# SCH_Weighing-Scale_2024-06-01.net
KiCad netlist of a schematic drawn in EasyEDA
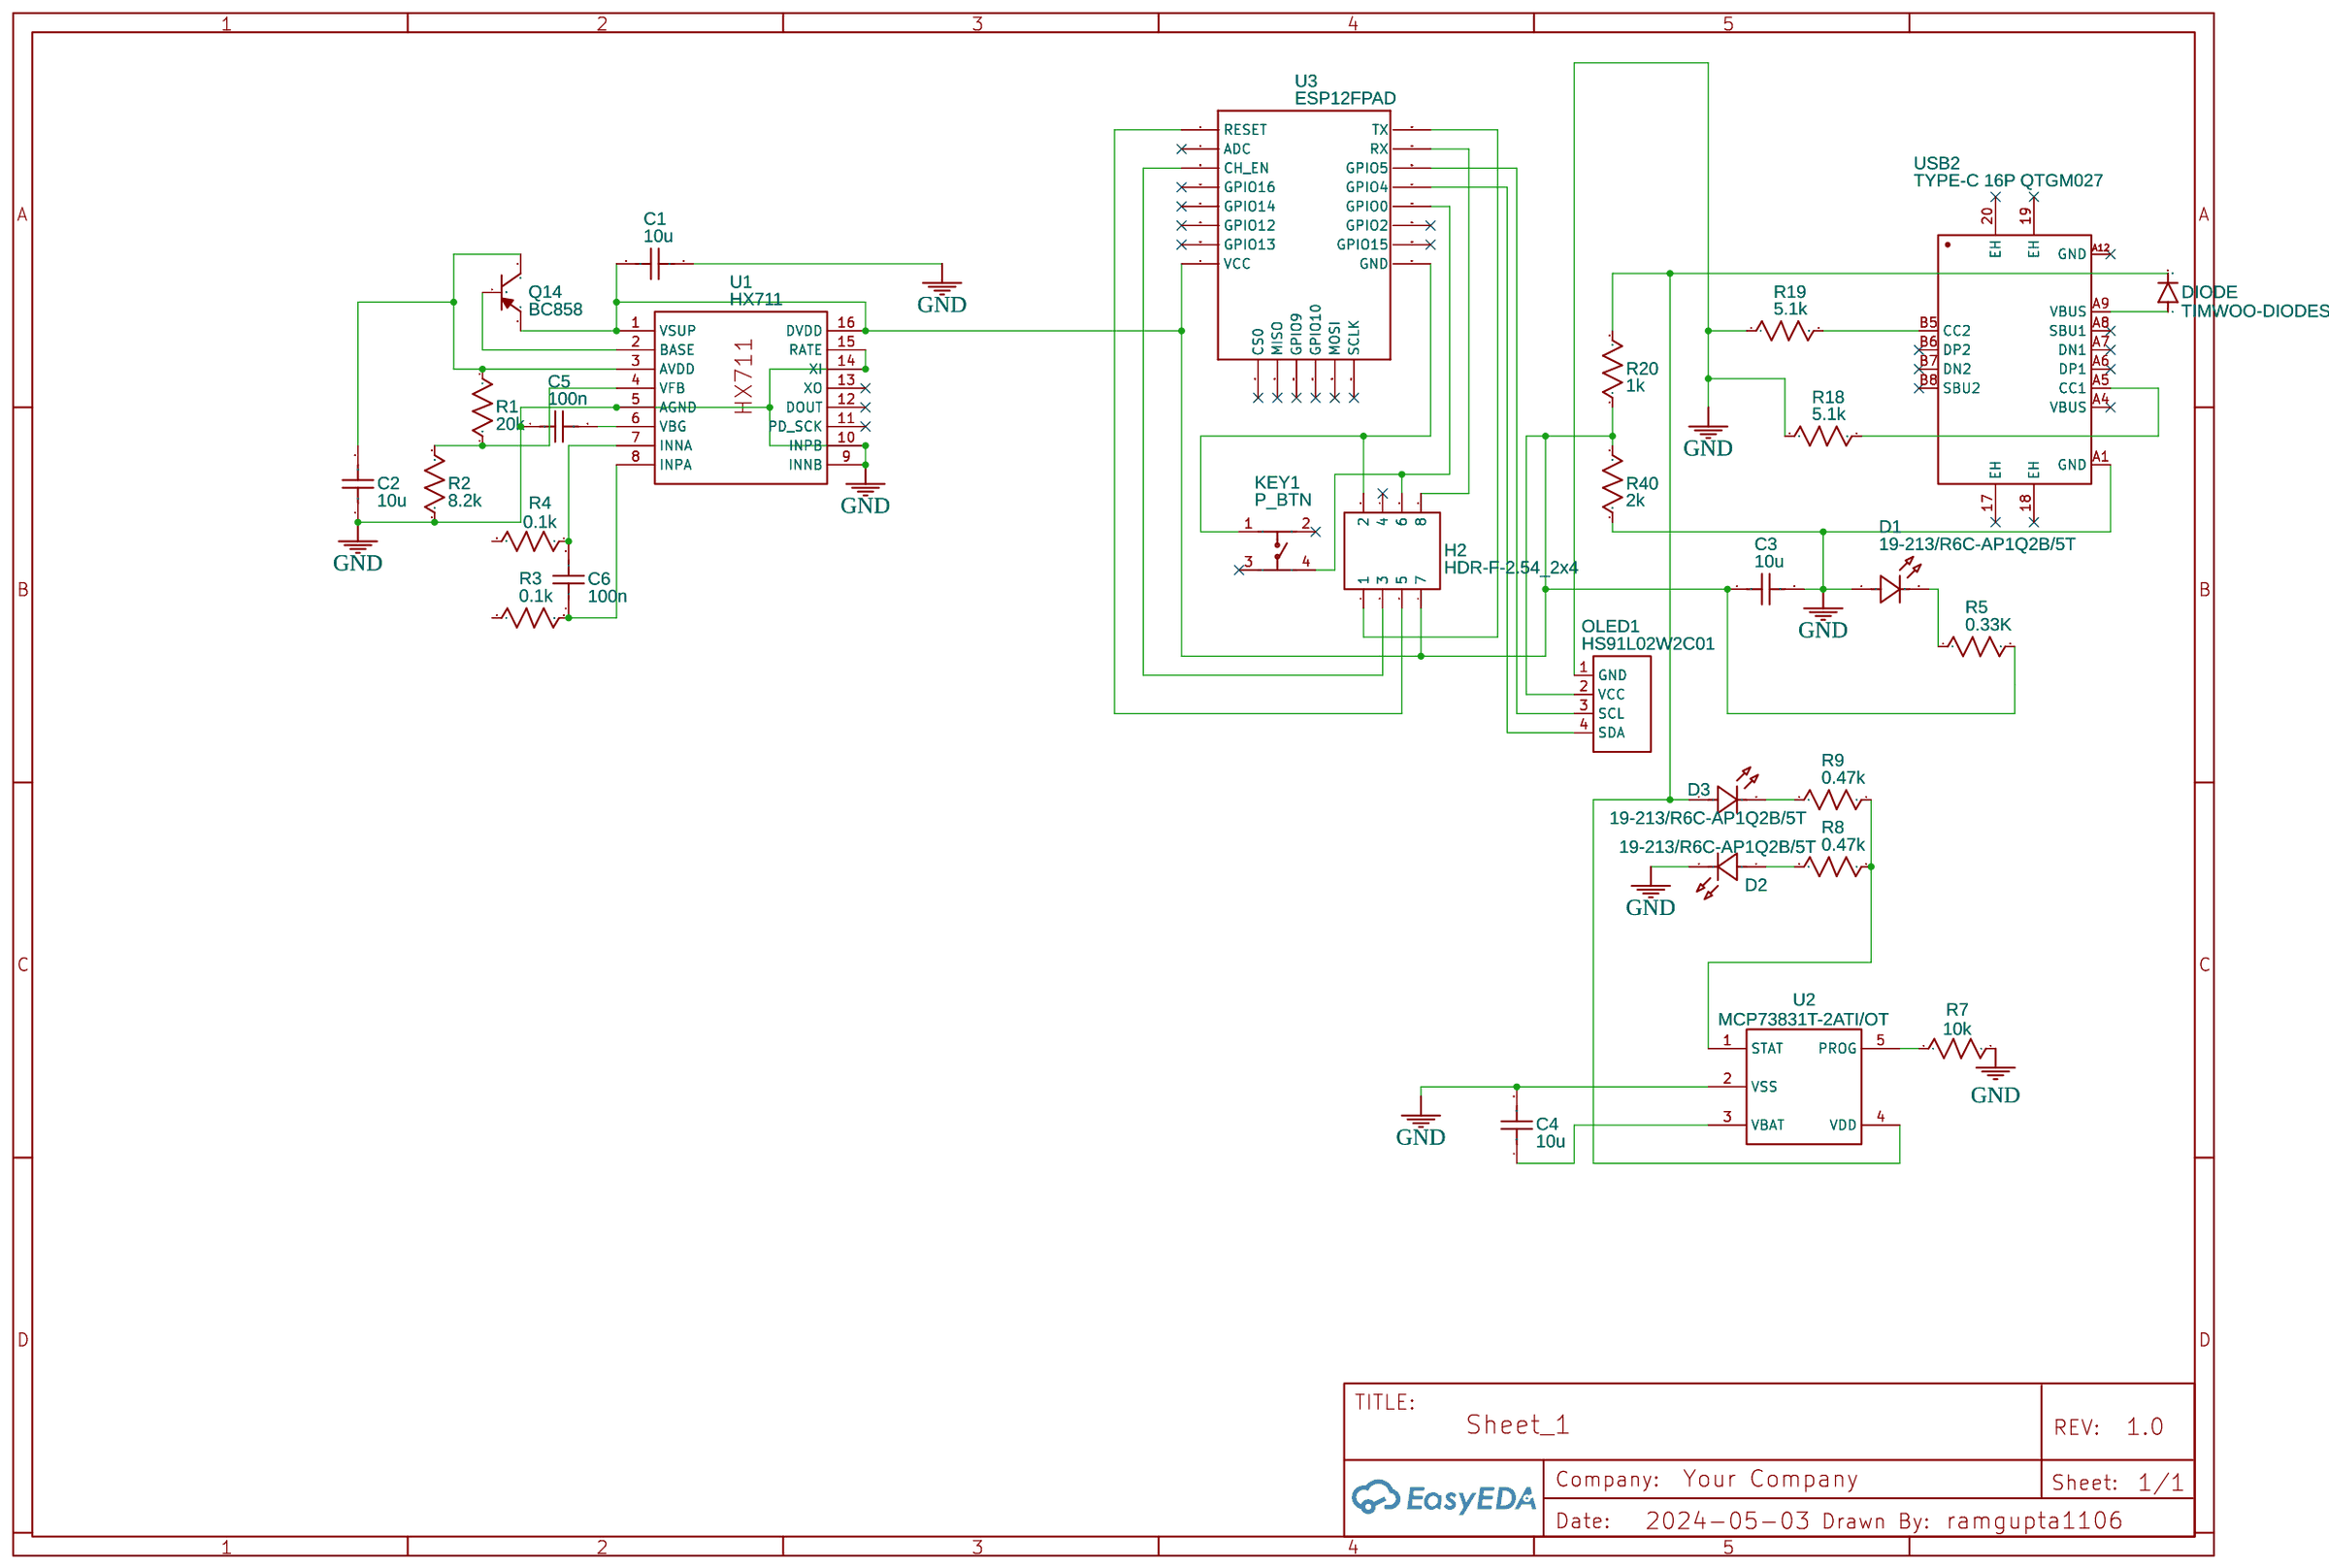
[diagram p0: schematic sheet]

(export (version "E")
  (design (tool "Eeschema 10.0.6"))
  (components
    (comp (ref "C1") (value "10u") (libsource (lib "") (part "C_0603_US_1")))
    (comp (ref "C2") (value "10u") (libsource (lib "") (part "C_0603_US")))
    (comp (ref "C3") (value "10u") (libsource (lib "") (part "C_0603_US_1")))
    (comp (ref "C4") (value "10u") (libsource (lib "") (part "C_0603_US")))
    (comp (ref "C5") (value "100n") (libsource (lib "") (part "C_0603_US_1")))
    (comp (ref "C6") (value "100n") (libsource (lib "") (part "C_0603_US")))
    (comp (ref "D1")
      (value "19-213/R6C-AP1Q2B/5T")
      (fields (field (name "Manufacturer") "EVERLIGHT(亿光)"))
      (libsource (lib "") (part "19-213/R6C-AP1Q2B/5T"))
    )
    (comp (ref "D2")
      (value "19-213/R6C-AP1Q2B/5T")
      (fields (field (name "Manufacturer") "EVERLIGHT(亿光)"))
      (libsource (lib "") (part "19-213/R6C-AP1Q2B/5T_1"))
    )
    (comp (ref "D3")
      (value "19-213/R6C-AP1Q2B/5T")
      (fields (field (name "Manufacturer") "EVERLIGHT(亿光)"))
      (libsource (lib "") (part "19-213/R6C-AP1Q2B/5T"))
    )
    (comp (ref "DIODE") (value "TIMWOO-DIODES_DIODEHV") (libsource (lib "") (part "TIMWOO-DIODES_DIODEHV")))
    (comp (ref "H2") (value "HDR-F-2.54_2x4") (libsource (lib "") (part "HDR-F-2.54_2x4")))
    (comp (ref "KEY1")
      (value "P_BTN")
      (fields (field (name "Manufacturer Part") "4pinTACTPCBTHTPushButton"))
      (libsource (lib "") (part "4PINTACTPCBTHTPUSHBUTTON"))
    )
    (comp (ref "OLED1")
      (value "HS91L02W2C01")
      (fields (field (name "Manufacturer") "HS(汉昇)"))
      (libsource (lib "") (part "HS91L02W2C01"))
    )
    (comp (ref "Q14")
      (value "BC858")
      (fields (field (name "Manufacturer") "HT(Shenzhen Jinyu Semicon)"))
      (libsource (lib "") (part "BC858"))
    )
    (comp (ref "R1") (value "20k") (libsource (lib "") (part "R_0603_US_3")))
    (comp (ref "R2") (value "8.2k") (libsource (lib "") (part "R_0603_US_2")))
    (comp (ref "R3") (value "0.1k") (libsource (lib "") (part "R_0603_US")))
    (comp (ref "R4") (value "0.1k") (libsource (lib "") (part "R_0603_US_1")))
    (comp (ref "R5") (value "0.33K") (libsource (lib "") (part "R_0603_US")))
    (comp (ref "R7") (value "10k") (libsource (lib "") (part "R_0603_US")))
    (comp (ref "R8") (value "0.47k") (libsource (lib "") (part "R_0603_US")))
    (comp (ref "R9") (value "0.47k") (libsource (lib "") (part "R_0603_US")))
    (comp (ref "R18") (value "5.1k") (libsource (lib "") (part "R_0603_US")))
    (comp (ref "R19") (value "5.1k") (libsource (lib "") (part "R_0603_US")))
    (comp (ref "R20") (value "1k") (libsource (lib "") (part "R_0603_US_2")))
    (comp (ref "R40") (value "2k") (libsource (lib "") (part "R_0603_US_2")))
    (comp (ref "U1")
      (value "HX711")
      (fields (field (name "Manufacturer") "AVIA(海芯科技)"))
      (libsource (lib "") (part "HX711"))
    )
    (comp (ref "U2")
      (value "MCP73831T-2ATI/OT")
      (fields (field (name "Manufacturer") "MICROCHIP(美国微芯)"))
      (libsource (lib "") (part "MCP73831T-2ATI/OT"))
    )
    (comp (ref "U3") (value "ESP12FPAD") (libsource (lib "") (part "ESP12FPAD")))
    (comp (ref "USB2")
      (value "TYPE-C 16P QTGM027")
      (fields (field (name "Manufacturer") "SHOU HAN(首韩)"))
      (libsource (lib "") (part "TYPE-C 16P QTGM027"))
    )
  )
  (nets
    (net (code "1") (name "GND") (class "Default")
      (node (ref "C1") (pin "2") (pinfunction "2_2") (pintype "unspecified"))
      (node (ref "C2") (pin "1") (pinfunction "1_1") (pintype "unspecified"))
      (node (ref "C3") (pin "2") (pinfunction "2_2") (pintype "unspecified"))
      (node (ref "C4") (pin "2") (pinfunction "2_2") (pintype "unspecified"))
      (node (ref "C5") (pin "1") (pinfunction "1_1") (pintype "unspecified"))
      (node (ref "D1") (pin "1") (pinfunction "A_1") (pintype "unspecified"))
      (node (ref "D2") (pin "2") (pinfunction "K_2") (pintype "unspecified"))
      (node (ref "OLED1") (pin "1") (pinfunction "GND_1") (pintype "unspecified"))
      (node (ref "R18") (pin "1") (pinfunction "1_1") (pintype "unspecified"))
      (node (ref "R19") (pin "1") (pinfunction "1_1") (pintype "unspecified"))
      (node (ref "R2") (pin "1") (pinfunction "1_1") (pintype "unspecified"))
      (node (ref "R40") (pin "1") (pinfunction "1_1") (pintype "unspecified"))
      (node (ref "R7") (pin "2") (pinfunction "2_2") (pintype "unspecified"))
      (node (ref "U1") (pin "10") (pinfunction "INPB_10") (pintype "unspecified"))
      (node (ref "U1") (pin "14") (pinfunction "XI_14") (pintype "unspecified"))
      (node (ref "U1") (pin "15") (pinfunction "RATE_15") (pintype "unspecified"))
      (node (ref "U1") (pin "5") (pinfunction "AGND_5") (pintype "unspecified"))
      (node (ref "U1") (pin "9") (pinfunction "INNB_9") (pintype "unspecified"))
      (node (ref "U2") (pin "2") (pinfunction "VSS_2") (pintype "unspecified"))
      (node (ref "USB2") (pin "A1") (pinfunction "GND_A1") (pintype "unspecified"))
    )
    (net (code "2") (name "Net-(D1-K)") (class "Default")
      (node (ref "D1") (pin "2") (pinfunction "K_2") (pintype "unspecified"))
      (node (ref "R5") (pin "1") (pinfunction "1_1") (pintype "unspecified"))
    )
    (net (code "3") (name "Net-(D2-A)") (class "Default")
      (node (ref "D2") (pin "1") (pinfunction "A_1") (pintype "unspecified"))
      (node (ref "R8") (pin "1") (pinfunction "1_1") (pintype "unspecified"))
    )
    (net (code "4") (name "Net-(D3-A)") (class "Default")
      (node (ref "D3") (pin "1") (pinfunction "A_1") (pintype "unspecified"))
      (node (ref "DIODE") (pin "C") (pinfunction "C_C") (pintype "bidirectional"))
      (node (ref "R20") (pin "2") (pinfunction "2_2") (pintype "unspecified"))
      (node (ref "U2") (pin "4") (pinfunction "VDD_4") (pintype "unspecified"))
    )
    (net (code "5") (name "Net-(D3-K)") (class "Default")
      (node (ref "D3") (pin "2") (pinfunction "K_2") (pintype "unspecified"))
      (node (ref "R9") (pin "1") (pinfunction "1_1") (pintype "unspecified"))
    )
    (net (code "6") (name "Net-(DIODE-PadA)") (class "Default")
      (node (ref "DIODE") (pin "A") (pinfunction "A_A") (pintype "bidirectional"))
      (node (ref "USB2") (pin "A9") (pinfunction "VBUS_A9") (pintype "unspecified"))
    )
    (net (code "7") (name "Net-(H2-Pad2)") (class "Default")
      (node (ref "H2") (pin "2") (pinfunction "2_2") (pintype "unspecified"))
      (node (ref "KEY1") (pin "1") (pinfunction "1_1") (pintype "unspecified"))
      (node (ref "U3") (pin "GND") (pinfunction "GND_GND") (pintype "bidirectional"))
    )
    (net (code "8") (name "Net-(H2-Pad5)") (class "Default")
      (node (ref "H2") (pin "5") (pinfunction "5_5") (pintype "unspecified"))
      (node (ref "U3") (pin "RESET") (pinfunction "RESET_RESET") (pintype "bidirectional"))
    )
    (net (code "9") (name "Net-(H2-Pad6)") (class "Default")
      (node (ref "H2") (pin "6") (pinfunction "6_6") (pintype "unspecified"))
      (node (ref "KEY1") (pin "4") (pinfunction "4_4") (pintype "unspecified"))
      (node (ref "U3") (pin "GPIO0") (pinfunction "GPIO0_GPIO0") (pintype "bidirectional"))
    )
    (net (code "10") (name "Net-(OLED1-SCL)") (class "Default")
      (node (ref "OLED1") (pin "3") (pinfunction "SCL_3") (pintype "unspecified"))
      (node (ref "U3") (pin "GPIO5") (pinfunction "GPIO5_GPIO5") (pintype "bidirectional"))
    )
    (net (code "11") (name "Net-(OLED1-SDA)") (class "Default")
      (node (ref "OLED1") (pin "4") (pinfunction "SDA_4") (pintype "unspecified"))
      (node (ref "U3") (pin "GPIO4") (pinfunction "GPIO4_GPIO4") (pintype "bidirectional"))
    )
    (net (code "12") (name "Net-(OLED1-VCC)") (class "Default")
      (node (ref "C1") (pin "1") (pinfunction "1_1") (pintype "unspecified"))
      (node (ref "C3") (pin "1") (pinfunction "1_1") (pintype "unspecified"))
      (node (ref "H2") (pin "7") (pinfunction "7_7") (pintype "unspecified"))
      (node (ref "OLED1") (pin "2") (pinfunction "VCC_2") (pintype "unspecified"))
      (node (ref "Q14") (pin "2") (pinfunction "E_2") (pintype "input"))
      (node (ref "R20") (pin "1") (pinfunction "1_1") (pintype "unspecified"))
      (node (ref "R40") (pin "2") (pinfunction "2_2") (pintype "unspecified"))
      (node (ref "R5") (pin "2") (pinfunction "2_2") (pintype "unspecified"))
      (node (ref "U1") (pin "1") (pinfunction "VSUP_1") (pintype "unspecified"))
      (node (ref "U1") (pin "16") (pinfunction "DVDD_16") (pintype "unspecified"))
      (node (ref "U3") (pin "VCC") (pinfunction "VCC_VCC") (pintype "bidirectional"))
    )
    (net (code "13") (name "Net-(Q14-B)") (class "Default")
      (node (ref "Q14") (pin "1") (pinfunction "B_1") (pintype "input"))
      (node (ref "U1") (pin "2") (pinfunction "BASE_2") (pintype "unspecified"))
    )
    (net (code "14") (name "Net-(Q14-C)") (class "Default")
      (node (ref "C2") (pin "2") (pinfunction "2_2") (pintype "unspecified"))
      (node (ref "Q14") (pin "3") (pinfunction "C_3") (pintype "input"))
      (node (ref "R1") (pin "1") (pinfunction "1_1") (pintype "unspecified"))
      (node (ref "U1") (pin "3") (pinfunction "AVDD_3") (pintype "unspecified"))
    )
    (net (code "15") (name "Net-(U1-INNA)") (class "Default")
      (node (ref "C6") (pin "2") (pinfunction "2_2") (pintype "unspecified"))
      (node (ref "R4") (pin "1") (pinfunction "1_1") (pintype "unspecified"))
      (node (ref "U1") (pin "7") (pinfunction "INNA_7") (pintype "unspecified"))
    )
    (net (code "16") (name "Net-(U1-INPA)") (class "Default")
      (node (ref "C6") (pin "1") (pinfunction "1_1") (pintype "unspecified"))
      (node (ref "R3") (pin "2") (pinfunction "2_2") (pintype "unspecified"))
      (node (ref "U1") (pin "8") (pinfunction "INPA_8") (pintype "unspecified"))
    )
    (net (code "17") (name "Net-(U1-VBG)") (class "Default")
      (node (ref "C5") (pin "2") (pinfunction "2_2") (pintype "unspecified"))
      (node (ref "U1") (pin "6") (pinfunction "VBG_6") (pintype "unspecified"))
    )
    (net (code "18") (name "Net-(U1-VFB)") (class "Default")
      (node (ref "R1") (pin "2") (pinfunction "2_2") (pintype "unspecified"))
      (node (ref "R2") (pin "2") (pinfunction "2_2") (pintype "unspecified"))
      (node (ref "U1") (pin "4") (pinfunction "VFB_4") (pintype "unspecified"))
    )
    (net (code "19") (name "Net-(U2-PROG)") (class "Default")
      (node (ref "R7") (pin "1") (pinfunction "1_1") (pintype "unspecified"))
      (node (ref "U2") (pin "5") (pinfunction "PROG_5") (pintype "unspecified"))
    )
    (net (code "20") (name "Net-(U2-STAT)") (class "Default")
      (node (ref "R8") (pin "2") (pinfunction "2_2") (pintype "unspecified"))
      (node (ref "R9") (pin "2") (pinfunction "2_2") (pintype "unspecified"))
      (node (ref "U2") (pin "1") (pinfunction "STAT_1") (pintype "unspecified"))
    )
    (net (code "21") (name "Net-(U2-VBAT)") (class "Default")
      (node (ref "C4") (pin "1") (pinfunction "1_1") (pintype "unspecified"))
      (node (ref "U2") (pin "3") (pinfunction "VBAT_3") (pintype "unspecified"))
    )
    (net (code "22") (name "Net-(U3-CH_EN)") (class "Default")
      (node (ref "H2") (pin "3") (pinfunction "3_3") (pintype "unspecified"))
      (node (ref "U3") (pin "CH_PD") (pinfunction "CH_EN_CH_PD") (pintype "bidirectional"))
    )
    (net (code "23") (name "Net-(U3-RX)") (class "Default")
      (node (ref "H2") (pin "8") (pinfunction "8_8") (pintype "unspecified"))
      (node (ref "U3") (pin "RXD0") (pinfunction "RX_RXD0") (pintype "bidirectional"))
    )
    (net (code "24") (name "Net-(U3-TX)") (class "Default")
      (node (ref "H2") (pin "1") (pinfunction "1_1") (pintype "unspecified"))
      (node (ref "U3") (pin "TXD0") (pinfunction "TX_TXD0") (pintype "bidirectional"))
    )
    (net (code "25") (name "Net-(USB2-CC1)") (class "Default")
      (node (ref "R18") (pin "2") (pinfunction "2_2") (pintype "unspecified"))
      (node (ref "USB2") (pin "A5") (pinfunction "CC1_A5") (pintype "unspecified"))
    )
    (net (code "26") (name "Net-(USB2-CC2)") (class "Default")
      (node (ref "R19") (pin "2") (pinfunction "2_2") (pintype "unspecified"))
      (node (ref "USB2") (pin "B5") (pinfunction "CC2_B5") (pintype "unspecified"))
    )
    (net (code "27") (name "unconnected-(H2-Pad4)") (class "Default")
      (node (ref "H2") (pin "4") (pinfunction "4_4") (pintype "unspecified+no_connect"))
    )
    (net (code "28") (name "unconnected-(KEY1-Pad2)") (class "Default")
      (node (ref "KEY1") (pin "2") (pinfunction "2_2") (pintype "unspecified+no_connect"))
    )
    (net (code "29") (name "unconnected-(KEY1-Pad3)") (class "Default")
      (node (ref "KEY1") (pin "3") (pinfunction "3_3") (pintype "unspecified+no_connect"))
    )
    (net (code "30") (name "unconnected-(R3-Pad1)") (class "Default")
      (node (ref "R3") (pin "1") (pinfunction "1_1") (pintype "unspecified"))
    )
    (net (code "31") (name "unconnected-(R4-Pad2)") (class "Default")
      (node (ref "R4") (pin "2") (pinfunction "2_2") (pintype "unspecified"))
    )
    (net (code "32") (name "unconnected-(U1-DOUT-Pad12)") (class "Default")
      (node (ref "U1") (pin "12") (pinfunction "DOUT_12") (pintype "unspecified+no_connect"))
    )
    (net (code "33") (name "unconnected-(U1-PD_SCK-Pad11)") (class "Default")
      (node (ref "U1") (pin "11") (pinfunction "PD_SCK_11") (pintype "unspecified+no_connect"))
    )
    (net (code "34") (name "unconnected-(U1-XO-Pad13)") (class "Default")
      (node (ref "U1") (pin "13") (pinfunction "XO_13") (pintype "unspecified+no_connect"))
    )
    (net (code "35") (name "unconnected-(U3-PadADC)") (class "Default")
      (node (ref "U3") (pin "ADC") (pinfunction "ADC_ADC") (pintype "bidirectional+no_connect"))
    )
    (net (code "36") (name "unconnected-(U3-PadCS0)") (class "Default")
      (node (ref "U3") (pin "CS0") (pinfunction "CS0_CS0") (pintype "bidirectional+no_connect"))
    )
    (net (code "37") (name "unconnected-(U3-PadGPIO2)") (class "Default")
      (node (ref "U3") (pin "GPIO2") (pinfunction "GPIO2_GPIO2") (pintype "bidirectional+no_connect"))
    )
    (net (code "38") (name "unconnected-(U3-PadGPIO9)") (class "Default")
      (node (ref "U3") (pin "GPIO9") (pinfunction "GPIO9_GPIO9") (pintype "bidirectional+no_connect"))
    )
    (net (code "39") (name "unconnected-(U3-PadGPIO10)") (class "Default")
      (node (ref "U3") (pin "GPIO10") (pinfunction "GPIO10_GPIO10") (pintype "bidirectional+no_connect"))
    )
    (net (code "40") (name "unconnected-(U3-PadGPIO12)") (class "Default")
      (node (ref "U3") (pin "GPIO12") (pinfunction "GPIO12_GPIO12") (pintype "bidirectional+no_connect"))
    )
    (net (code "41") (name "unconnected-(U3-PadGPIO13)") (class "Default")
      (node (ref "U3") (pin "GPIO13") (pinfunction "GPIO13_GPIO13") (pintype "bidirectional+no_connect"))
    )
    (net (code "42") (name "unconnected-(U3-PadGPIO14)") (class "Default")
      (node (ref "U3") (pin "GPIO14") (pinfunction "GPIO14_GPIO14") (pintype "bidirectional+no_connect"))
    )
    (net (code "43") (name "unconnected-(U3-PadGPIO15)") (class "Default")
      (node (ref "U3") (pin "GPIO15") (pinfunction "GPIO15_GPIO15") (pintype "bidirectional+no_connect"))
    )
    (net (code "44") (name "unconnected-(U3-PadGPIO16)") (class "Default")
      (node (ref "U3") (pin "GPIO16") (pinfunction "GPIO16_GPIO16") (pintype "bidirectional+no_connect"))
    )
    (net (code "45") (name "unconnected-(U3-PadMISO)") (class "Default")
      (node (ref "U3") (pin "MISO") (pinfunction "MISO_MISO") (pintype "bidirectional+no_connect"))
    )
    (net (code "46") (name "unconnected-(U3-PadMOSI)") (class "Default")
      (node (ref "U3") (pin "MOSI") (pinfunction "MOSI_MOSI") (pintype "bidirectional+no_connect"))
    )
    (net (code "47") (name "unconnected-(U3-PadSCLK)") (class "Default")
      (node (ref "U3") (pin "SCLK") (pinfunction "SCLK_SCLK") (pintype "bidirectional+no_connect"))
    )
    (net (code "48") (name "unconnected-(USB2-DN1-PadA7)") (class "Default")
      (node (ref "USB2") (pin "A7") (pinfunction "DN1_A7") (pintype "unspecified+no_connect"))
    )
    (net (code "49") (name "unconnected-(USB2-DN2-PadB7)") (class "Default")
      (node (ref "USB2") (pin "B7") (pinfunction "DN2_B7") (pintype "unspecified+no_connect"))
    )
    (net (code "50") (name "unconnected-(USB2-DP1-PadA6)") (class "Default")
      (node (ref "USB2") (pin "A6") (pinfunction "DP1_A6") (pintype "unspecified+no_connect"))
    )
    (net (code "51") (name "unconnected-(USB2-DP2-PadB6)") (class "Default")
      (node (ref "USB2") (pin "B6") (pinfunction "DP2_B6") (pintype "unspecified+no_connect"))
    )
    (net (code "52") (name "unconnected-(USB2-EH-Pad17)") (class "Default")
      (node (ref "USB2") (pin "17") (pinfunction "EH_17") (pintype "unspecified+no_connect"))
    )
    (net (code "53") (name "unconnected-(USB2-EH-Pad18)") (class "Default")
      (node (ref "USB2") (pin "18") (pinfunction "EH_18") (pintype "unspecified+no_connect"))
    )
    (net (code "54") (name "unconnected-(USB2-EH-Pad19)") (class "Default")
      (node (ref "USB2") (pin "19") (pinfunction "EH_19") (pintype "unspecified+no_connect"))
    )
    (net (code "55") (name "unconnected-(USB2-EH-Pad20)") (class "Default")
      (node (ref "USB2") (pin "20") (pinfunction "EH_20") (pintype "unspecified+no_connect"))
    )
    (net (code "56") (name "unconnected-(USB2-GND-PadA12)") (class "Default")
      (node (ref "USB2") (pin "A12") (pinfunction "GND_A12") (pintype "unspecified+no_connect"))
    )
    (net (code "57") (name "unconnected-(USB2-SBU1-PadA8)") (class "Default")
      (node (ref "USB2") (pin "A8") (pinfunction "SBU1_A8") (pintype "unspecified+no_connect"))
    )
    (net (code "58") (name "unconnected-(USB2-SBU2-PadB8)") (class "Default")
      (node (ref "USB2") (pin "B8") (pinfunction "SBU2_B8") (pintype "unspecified+no_connect"))
    )
    (net (code "59") (name "unconnected-(USB2-VBUS-PadA4)") (class "Default")
      (node (ref "USB2") (pin "A4") (pinfunction "VBUS_A4") (pintype "unspecified+no_connect"))
    )
  )
)
